# 1_panel.net
KiCad netlist of a schematic drawn in Altium Designer
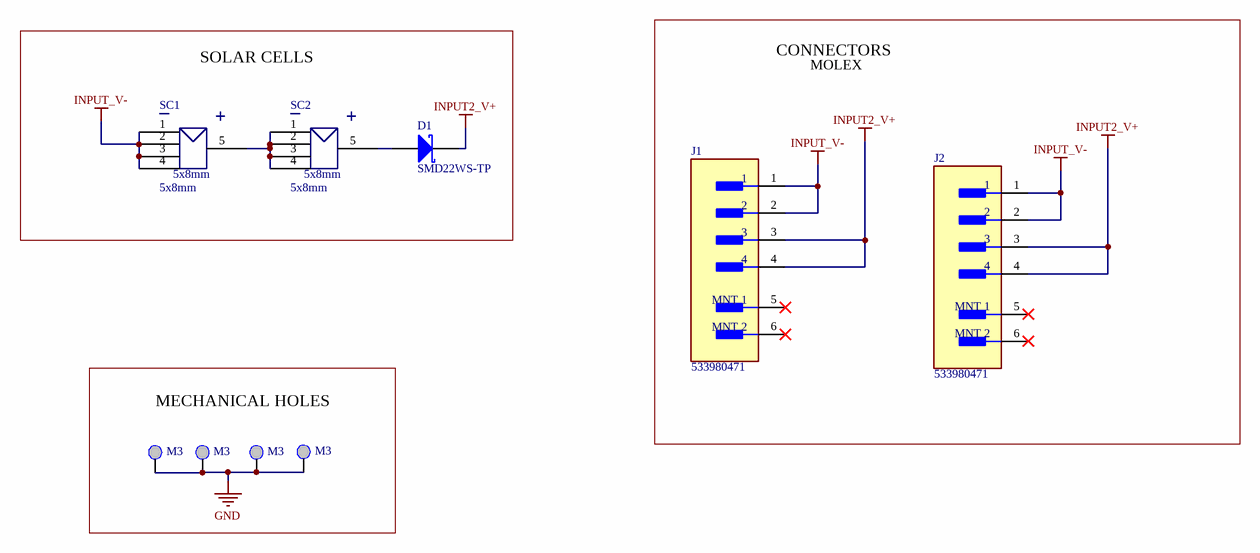
[diagram p0: 1_panel.schdoc]

(export (version "E")
  (design (tool "Eeschema 10.0.6"))
  (components
    (comp (ref "D1")
      (value "SMD22WS-TP")
      (footprint "SOD323F")
      (description "Diode Schottky 20 V 2A Surface Mount SOD-323")
      (libsource (lib "schematics_library_legacy") (part "DIODE_SCHOTTKY_20V_2A_SMD22WS-TP"))
    )
    (comp (ref "J1")
      (value "533980471")
      (footprint "FP-533980471-MFG")
      (description "CONN HEADER SMD 4POS 1.25MM")
      (fields
        (field (name "OCTOPART") "https://octopart.com/53398-0471-molex-655296")
        (field (name "MANUFACTURER") "Molex")
      )
      (libsource (lib "Altium Content Vault") (part "3b6f738a5616415d78381ad43816e4a"))
    )
    (comp (ref "J2")
      (value "533980471")
      (footprint "FP-533980471-MFG")
      (description "CONN HEADER SMD 4POS 1.25MM")
      (fields
        (field (name "OCTOPART") "https://octopart.com/53398-0471-molex-655296")
        (field (name "MANUFACTURER") "Molex")
      )
      (libsource (lib "Altium Content Vault") (part "3b6f738a5616415d78381ad43816e4a"))
    )
    (comp (ref "MEC1")
      (value "M3")
      (footprint "HOLE6x6mm")
      (description "M3 hole")
      (libsource (lib "schematics_library_legacy") (part "M3 hole"))
    )
    (comp (ref "MEC2")
      (value "M3")
      (footprint "HOLE6x6mm")
      (description "M3 hole")
      (libsource (lib "schematics_library_legacy") (part "M3 hole"))
    )
    (comp (ref "MEC3")
      (value "M3")
      (footprint "HOLE6x6mm")
      (description "M3 hole")
      (libsource (lib "schematics_library_legacy") (part "M3 hole"))
    )
    (comp (ref "MEC4")
      (value "M3")
      (footprint "HOLE6x6mm")
      (description "M3 hole")
      (libsource (lib "schematics_library_legacy") (part "M3 hole"))
    )
    (comp (ref "SC1")
      (value "5x8mm")
      (footprint "SOLAR_CELL_SIDES")
      (fields (field (name "MANUFACTURER") "Yim Space"))
      (libsource (lib "Schlib1") (part "SOLAR CELL"))
    )
    (comp (ref "SC2")
      (value "5x8mm")
      (footprint "SOLAR_CELL_SIDES")
      (fields (field (name "MANUFACTURER") "Yim Space"))
      (libsource (lib "Schlib1") (part "SOLAR CELL"))
    )
  )
  (nets
    (net (code "1") (name "GND") (class "Default")
      (node (ref "MEC1") (pin "0") (pinfunction "0_0") (pintype "passive"))
      (node (ref "MEC2") (pin "0") (pinfunction "0_0") (pintype "passive"))
      (node (ref "MEC3") (pin "0") (pinfunction "0_0") (pintype "passive"))
      (node (ref "MEC4") (pin "0") (pinfunction "0_0") (pintype "passive"))
    )
    (net (code "2") (name "INPUT2_V+") (class "Default")
      (node (ref "D1") (pin "1") (pinfunction "K_1") (pintype "passive"))
      (node (ref "J1") (pin "3") (pinfunction "3_3") (pintype "passive"))
      (node (ref "J1") (pin "4") (pinfunction "4_4") (pintype "passive"))
      (node (ref "J2") (pin "3") (pinfunction "3_3") (pintype "passive"))
      (node (ref "J2") (pin "4") (pinfunction "4_4") (pintype "passive"))
    )
    (net (code "3") (name "INPUT_V-") (class "Default")
      (node (ref "J1") (pin "1") (pinfunction "1_1") (pintype "passive"))
      (node (ref "J1") (pin "2") (pinfunction "2_2") (pintype "passive"))
      (node (ref "J2") (pin "1") (pinfunction "1_1") (pintype "passive"))
      (node (ref "J2") (pin "2") (pinfunction "2_2") (pintype "passive"))
      (node (ref "SC1") (pin "1") (pinfunction "V+_1") (pintype "power_in"))
      (node (ref "SC1") (pin "2") (pinfunction "V-_2") (pintype "power_in"))
      (node (ref "SC1") (pin "3") (pinfunction "3_3") (pintype "passive"))
      (node (ref "SC1") (pin "4") (pinfunction "4_4") (pintype "passive"))
    )
    (net (code "4") (name "Net-(D1-A)") (class "Default")
      (node (ref "D1") (pin "2") (pinfunction "A_2") (pintype "passive"))
      (node (ref "SC2") (pin "5") (pinfunction "5_5") (pintype "passive"))
    )
    (net (code "5") (name "Net-(SC2-V+)") (class "Default")
      (node (ref "SC1") (pin "5") (pinfunction "5_5") (pintype "passive"))
      (node (ref "SC2") (pin "1") (pinfunction "V+_1") (pintype "power_in"))
      (node (ref "SC2") (pin "2") (pinfunction "V-_2") (pintype "power_in"))
      (node (ref "SC2") (pin "3") (pinfunction "3_3") (pintype "passive"))
      (node (ref "SC2") (pin "4") (pinfunction "4_4") (pintype "passive"))
    )
    (net (code "6") (name "unconnected-(J1-MNT_1-Pad5)") (class "Default")
      (node (ref "J1") (pin "5") (pinfunction "MNT_1_5") (pintype "passive+no_connect"))
    )
    (net (code "7") (name "unconnected-(J1-MNT_2-Pad6)") (class "Default")
      (node (ref "J1") (pin "6") (pinfunction "MNT_2_6") (pintype "passive+no_connect"))
    )
    (net (code "8") (name "unconnected-(J2-MNT_1-Pad5)") (class "Default")
      (node (ref "J2") (pin "5") (pinfunction "MNT_1_5") (pintype "passive+no_connect"))
    )
    (net (code "9") (name "unconnected-(J2-MNT_2-Pad6)") (class "Default")
      (node (ref "J2") (pin "6") (pinfunction "MNT_2_6") (pintype "passive+no_connect"))
    )
  )
)
